# SENSE_AMP_-_4_CH.net
KiCad netlist of a schematic drawn in Altium Designer
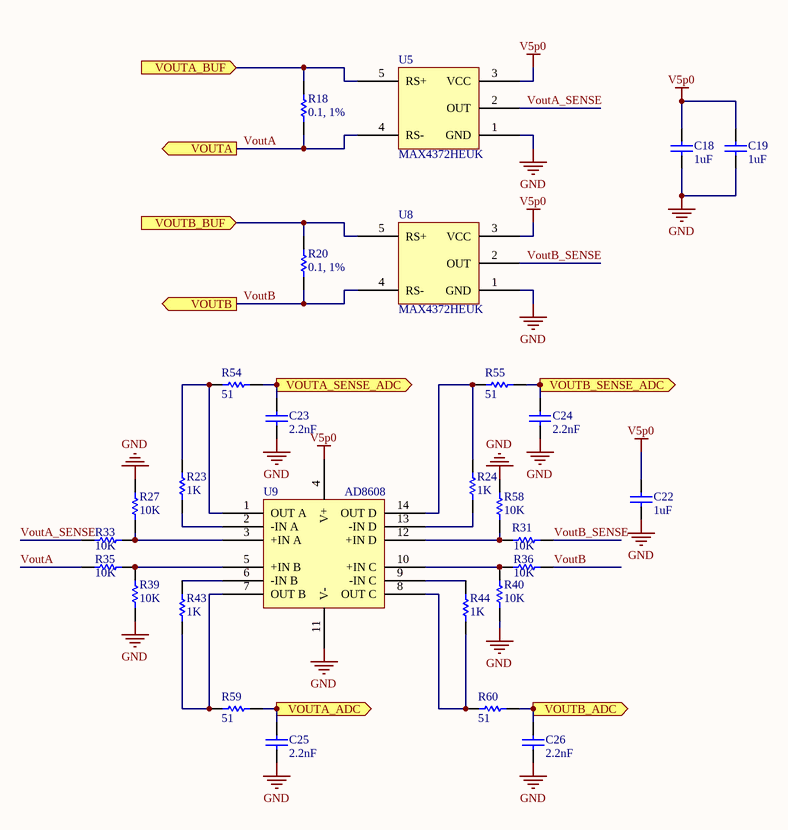
[diagram p0: SENSE AMP - 4 CH.SchDoc]

(export (version "E")
  (design (tool "Eeschema 10.0.6"))
  (components
    (comp (ref "C18")
      (value "1uF")
      (footprint "CAPC01005(0402)22_N")
      (fields (field (name "Comment") "CAP, 0402, 1uF"))
      (libsource (lib "Components") (part "CAP, 0402, 1uF"))
    )
    (comp (ref "C19")
      (value "1uF")
      (footprint "CAPC01005(0402)22_N")
      (fields (field (name "Comment") "CAP, 0402, 1uF"))
      (libsource (lib "Components") (part "CAP, 0402, 1uF"))
    )
    (comp (ref "C22")
      (value "1uF")
      (footprint "CAPC01005(0402)22_N")
      (fields (field (name "Comment") "CAP, 0402, 1uF"))
      (libsource (lib "Components") (part "CAP, 0402, 1uF"))
    )
    (comp (ref "C23")
      (value "2.2nF")
      (footprint "CAPC01005(0402)22_N")
      (fields
        (field (name "TOLERANCE") "±10%")
        (field (name "MANUFACTURER") "Taiyo Yuden")
        (field (name "MANUFACTURER PART NUMBER") "UMK105B7222KV-F")
      )
      (libsource (lib "Components") (part "CAP, 0402, 2.2nF"))
    )
    (comp (ref "C24")
      (value "2.2nF")
      (footprint "CAPC01005(0402)22_N")
      (fields
        (field (name "TOLERANCE") "±10%")
        (field (name "MANUFACTURER") "Taiyo Yuden")
        (field (name "MANUFACTURER PART NUMBER") "UMK105B7222KV-F")
      )
      (libsource (lib "Components") (part "CAP, 0402, 2.2nF"))
    )
    (comp (ref "C25")
      (value "2.2nF")
      (footprint "CAPC01005(0402)22_N")
      (fields
        (field (name "TOLERANCE") "±10%")
        (field (name "MANUFACTURER") "Taiyo Yuden")
        (field (name "MANUFACTURER PART NUMBER") "UMK105B7222KV-F")
      )
      (libsource (lib "Components") (part "CAP, 0402, 2.2nF"))
    )
    (comp (ref "C26")
      (value "2.2nF")
      (footprint "CAPC01005(0402)22_N")
      (fields
        (field (name "TOLERANCE") "±10%")
        (field (name "MANUFACTURER") "Taiyo Yuden")
        (field (name "MANUFACTURER PART NUMBER") "UMK105B7222KV-F")
      )
      (libsource (lib "Components") (part "CAP, 0402, 2.2nF"))
    )
    (comp (ref "R18")
      (value "0.1, 1%")
      (footprint "RES, 0603")
      (fields
        (field (name "TOLERANCE") "±1%")
        (field (name "MANUFACTURER") "Panasonic Electronic Components")
        (field (name "MANUFACTURER PART NUMBER") "ERJ-3RSFR10V")
      )
      (libsource (lib "Components") (part "RES, 0603, 0.1, 1%"))
    )
    (comp (ref "R20")
      (value "0.1, 1%")
      (footprint "RES, 0603")
      (fields
        (field (name "TOLERANCE") "±1%")
        (field (name "MANUFACTURER") "Panasonic Electronic Components")
        (field (name "MANUFACTURER PART NUMBER") "ERJ-3RSFR10V")
      )
      (libsource (lib "Components") (part "RES, 0603, 0.1, 1%"))
    )
    (comp (ref "R23")
      (value "1K")
      (footprint "RES, 0603")
      (description "Resistor, 0603, 1/10W, 1K ohm")
      (fields
        (field (name "MANUFACTURER") "Panasonic Electronic Components")
        (field (name "MANUFACTURER PART NUMBER") "ERJ-3EKF1001V")
      )
      (libsource (lib "Resistors0603") (part "RES_0603_1K"))
    )
    (comp (ref "R24")
      (value "1K")
      (footprint "RES, 0603")
      (description "Resistor, 0603, 1/10W, 1K ohm")
      (fields
        (field (name "MANUFACTURER") "Panasonic Electronic Components")
        (field (name "MANUFACTURER PART NUMBER") "ERJ-3EKF1001V")
      )
      (libsource (lib "Resistors0603") (part "RES_0603_1K"))
    )
    (comp (ref "R27")
      (value "10K")
      (footprint "RES, 0603")
      (description "Resistor, 0603, 1/10W, 10K ohm")
      (fields
        (field (name "MANUFACTURER") "Panasonic Electronic Components")
        (field (name "MANUFACTURER PART NUMBER") "ERJ-3EKF1002V")
      )
      (libsource (lib "Resistors0603") (part "RES_0603_10K"))
    )
    (comp (ref "R31")
      (value "10K")
      (footprint "RES, 0603")
      (description "Resistor, 0603, 1/10W, 10K ohm")
      (fields
        (field (name "MANUFACTURER") "Panasonic Electronic Components")
        (field (name "MANUFACTURER PART NUMBER") "ERJ-3EKF1002V")
      )
      (libsource (lib "Resistors0603") (part "RES_0603_10K"))
    )
    (comp (ref "R33")
      (value "10K")
      (footprint "RES, 0603")
      (description "Resistor, 0603, 1/10W, 10K ohm")
      (fields
        (field (name "MANUFACTURER") "Panasonic Electronic Components")
        (field (name "MANUFACTURER PART NUMBER") "ERJ-3EKF1002V")
      )
      (libsource (lib "Resistors0603") (part "RES_0603_10K"))
    )
    (comp (ref "R35")
      (value "10K")
      (footprint "RES, 0603")
      (description "Resistor, 0603, 1/10W, 10K ohm")
      (fields
        (field (name "MANUFACTURER") "Panasonic Electronic Components")
        (field (name "MANUFACTURER PART NUMBER") "ERJ-3EKF1002V")
      )
      (libsource (lib "Resistors0603") (part "RES_0603_10K"))
    )
    (comp (ref "R36")
      (value "10K")
      (footprint "RES, 0603")
      (description "Resistor, 0603, 1/10W, 10K ohm")
      (fields
        (field (name "MANUFACTURER") "Panasonic Electronic Components")
        (field (name "MANUFACTURER PART NUMBER") "ERJ-3EKF1002V")
      )
      (libsource (lib "Resistors0603") (part "RES_0603_10K"))
    )
    (comp (ref "R39")
      (value "10K")
      (footprint "RES, 0603")
      (description "Resistor, 0603, 1/10W, 10K ohm")
      (fields
        (field (name "MANUFACTURER") "Panasonic Electronic Components")
        (field (name "MANUFACTURER PART NUMBER") "ERJ-3EKF1002V")
      )
      (libsource (lib "Resistors0603") (part "RES_0603_10K"))
    )
    (comp (ref "R40")
      (value "10K")
      (footprint "RES, 0603")
      (description "Resistor, 0603, 1/10W, 10K ohm")
      (fields
        (field (name "MANUFACTURER") "Panasonic Electronic Components")
        (field (name "MANUFACTURER PART NUMBER") "ERJ-3EKF1002V")
      )
      (libsource (lib "Resistors0603") (part "RES_0603_10K"))
    )
    (comp (ref "R43")
      (value "1K")
      (footprint "RES, 0603")
      (description "Resistor, 0603, 1/10W, 1K ohm")
      (fields
        (field (name "MANUFACTURER") "Panasonic Electronic Components")
        (field (name "MANUFACTURER PART NUMBER") "ERJ-3EKF1001V")
      )
      (libsource (lib "Resistors0603") (part "RES_0603_1K"))
    )
    (comp (ref "R44")
      (value "1K")
      (footprint "RES, 0603")
      (description "Resistor, 0603, 1/10W, 1K ohm")
      (fields
        (field (name "MANUFACTURER") "Panasonic Electronic Components")
        (field (name "MANUFACTURER PART NUMBER") "ERJ-3EKF1001V")
      )
      (libsource (lib "Resistors0603") (part "RES_0603_1K"))
    )
    (comp (ref "R54")
      (value "51")
      (footprint "RES, 0603")
      (description "Resistor, 0603, 1/10W, 51 ohm")
      (fields
        (field (name "MANUFACTURER") "Panasonic Electronic Components")
        (field (name "MANUFACTURER PART NUMBER") "ERJ-3EKF51R0V")
      )
      (libsource (lib "Resistors0603") (part "RES_0603_51"))
    )
    (comp (ref "R55")
      (value "51")
      (footprint "RES, 0603")
      (description "Resistor, 0603, 1/10W, 51 ohm")
      (fields
        (field (name "MANUFACTURER") "Panasonic Electronic Components")
        (field (name "MANUFACTURER PART NUMBER") "ERJ-3EKF51R0V")
      )
      (libsource (lib "Resistors0603") (part "RES_0603_51"))
    )
    (comp (ref "R58")
      (value "10K")
      (footprint "RES, 0603")
      (description "Resistor, 0603, 1/10W, 10K ohm")
      (fields
        (field (name "MANUFACTURER") "Panasonic Electronic Components")
        (field (name "MANUFACTURER PART NUMBER") "ERJ-3EKF1002V")
      )
      (libsource (lib "Resistors0603") (part "RES_0603_10K"))
    )
    (comp (ref "R59")
      (value "51")
      (footprint "RES, 0603")
      (description "Resistor, 0603, 1/10W, 51 ohm")
      (fields
        (field (name "MANUFACTURER") "Panasonic Electronic Components")
        (field (name "MANUFACTURER PART NUMBER") "ERJ-3EKF51R0V")
      )
      (libsource (lib "Resistors0603") (part "RES_0603_51"))
    )
    (comp (ref "R60")
      (value "51")
      (footprint "RES, 0603")
      (description "Resistor, 0603, 1/10W, 51 ohm")
      (fields
        (field (name "MANUFACTURER") "Panasonic Electronic Components")
        (field (name "MANUFACTURER PART NUMBER") "ERJ-3EKF51R0V")
      )
      (libsource (lib "Resistors0603") (part "RES_0603_51"))
    )
    (comp (ref "U5")
      (value "MAX4372HEUK")
      (footprint "SOT23-5, MAX4372H")
      (fields (field (name "MANUFACTURER") "Maxim"))
      (libsource (lib "Components") (part "MAX4372H, Current-Sense, SOT23"))
    )
    (comp (ref "U8")
      (value "MAX4372HEUK")
      (footprint "SOT23-5, MAX4372H")
      (fields (field (name "MANUFACTURER") "Maxim"))
      (libsource (lib "Components") (part "MAX4372H, Current-Sense, SOT23"))
    )
    (comp (ref "U9")
      (value "AD8608")
      (footprint "TSOP65P640X120-14N")
      (description "Quad Op-Amp")
      (fields
        (field (name "MANUFACTURER") "Analog Devices Inc")
        (field (name "MANUFACTURER PART NUMBER") "AD8608ARZ-REEL")
      )
      (libsource (lib "Components") (part "AD8608"))
    )
  )
  (nets
    (net (code "1") (name "/VOUTA_ADC") (class "Default")
      (node (ref "C25") (pin "2") (pinfunction "2_2") (pintype "passive"))
      (node (ref "R59") (pin "2") (pinfunction "2_2") (pintype "passive"))
    )
    (net (code "2") (name "/VOUTA_BUF") (class "Default")
      (node (ref "R18") (pin "2") (pinfunction "2_2") (pintype "passive"))
      (node (ref "U5") (pin "5") (pinfunction "RS+_5") (pintype "passive"))
    )
    (net (code "3") (name "/VOUTA_SENSE_ADC") (class "Default")
      (node (ref "C23") (pin "2") (pinfunction "2_2") (pintype "passive"))
      (node (ref "R54") (pin "2") (pinfunction "2_2") (pintype "passive"))
    )
    (net (code "4") (name "/VOUTB_ADC") (class "Default")
      (node (ref "C26") (pin "2") (pinfunction "2_2") (pintype "passive"))
      (node (ref "R60") (pin "2") (pinfunction "2_2") (pintype "passive"))
    )
    (net (code "5") (name "/VOUTB_BUF") (class "Default")
      (node (ref "R20") (pin "2") (pinfunction "2_2") (pintype "passive"))
      (node (ref "U8") (pin "5") (pinfunction "RS+_5") (pintype "passive"))
    )
    (net (code "6") (name "/VOUTB_SENSE_ADC") (class "Default")
      (node (ref "C24") (pin "2") (pinfunction "2_2") (pintype "passive"))
      (node (ref "R55") (pin "2") (pinfunction "2_2") (pintype "passive"))
    )
    (net (code "7") (name "/VoutA") (class "Default")
      (node (ref "R18") (pin "1") (pinfunction "1_1") (pintype "passive"))
      (node (ref "R35") (pin "1") (pinfunction "1_1") (pintype "passive"))
      (node (ref "U5") (pin "4") (pinfunction "RS-_4") (pintype "passive"))
    )
    (net (code "8") (name "/VoutA_SENSE") (class "Default")
      (node (ref "R33") (pin "1") (pinfunction "1_1") (pintype "passive"))
      (node (ref "U5") (pin "2") (pinfunction "OUT_2") (pintype "passive"))
    )
    (net (code "9") (name "/VoutB") (class "Default")
      (node (ref "R20") (pin "1") (pinfunction "1_1") (pintype "passive"))
      (node (ref "R36") (pin "1") (pinfunction "1_1") (pintype "passive"))
      (node (ref "U8") (pin "4") (pinfunction "RS-_4") (pintype "passive"))
    )
    (net (code "10") (name "/VoutB_SENSE") (class "Default")
      (node (ref "R31") (pin "1") (pinfunction "1_1") (pintype "passive"))
      (node (ref "U8") (pin "2") (pinfunction "OUT_2") (pintype "passive"))
    )
    (net (code "11") (name "GND") (class "Default")
      (node (ref "C18") (pin "1") (pinfunction "1_1") (pintype "passive"))
      (node (ref "C19") (pin "1") (pinfunction "1_1") (pintype "passive"))
      (node (ref "C22") (pin "1") (pinfunction "1_1") (pintype "passive"))
      (node (ref "C23") (pin "1") (pinfunction "1_1") (pintype "passive"))
      (node (ref "C24") (pin "1") (pinfunction "1_1") (pintype "passive"))
      (node (ref "C25") (pin "1") (pinfunction "1_1") (pintype "passive"))
      (node (ref "C26") (pin "1") (pinfunction "1_1") (pintype "passive"))
      (node (ref "R27") (pin "2") (pinfunction "2_2") (pintype "passive"))
      (node (ref "R39") (pin "1") (pinfunction "1_1") (pintype "passive"))
      (node (ref "R40") (pin "2") (pinfunction "2_2") (pintype "passive"))
      (node (ref "R58") (pin "1") (pinfunction "1_1") (pintype "passive"))
      (node (ref "U5") (pin "1") (pinfunction "GND_1") (pintype "passive"))
      (node (ref "U8") (pin "1") (pinfunction "GND_1") (pintype "passive"))
      (node (ref "U9") (pin "11") (pinfunction "V-_11") (pintype "passive"))
    )
    (net (code "12") (name "Net-(U9-+IN_A)") (class "Default")
      (node (ref "R27") (pin "1") (pinfunction "1_1") (pintype "passive"))
      (node (ref "R33") (pin "2") (pinfunction "2_2") (pintype "passive"))
      (node (ref "U9") (pin "3") (pinfunction "+IN_A_3") (pintype "passive"))
    )
    (net (code "13") (name "Net-(U9-+IN_B)") (class "Default")
      (node (ref "R35") (pin "2") (pinfunction "2_2") (pintype "passive"))
      (node (ref "R39") (pin "2") (pinfunction "2_2") (pintype "passive"))
      (node (ref "U9") (pin "5") (pinfunction "+IN_B_5") (pintype "passive"))
    )
    (net (code "14") (name "Net-(U9-+IN_C)") (class "Default")
      (node (ref "R36") (pin "2") (pinfunction "2_2") (pintype "passive"))
      (node (ref "R40") (pin "1") (pinfunction "1_1") (pintype "passive"))
      (node (ref "U9") (pin "10") (pinfunction "+IN_C_10") (pintype "passive"))
    )
    (net (code "15") (name "Net-(U9-+IN_D)") (class "Default")
      (node (ref "R31") (pin "2") (pinfunction "2_2") (pintype "passive"))
      (node (ref "R58") (pin "2") (pinfunction "2_2") (pintype "passive"))
      (node (ref "U9") (pin "12") (pinfunction "+IN_D_12") (pintype "passive"))
    )
    (net (code "16") (name "Net-(U9--IN_A)") (class "Default")
      (node (ref "R23") (pin "1") (pinfunction "1_1") (pintype "passive"))
      (node (ref "U9") (pin "2") (pinfunction "-IN_A_2") (pintype "passive"))
    )
    (net (code "17") (name "Net-(U9--IN_B)") (class "Default")
      (node (ref "R43") (pin "2") (pinfunction "2_2") (pintype "passive"))
      (node (ref "U9") (pin "6") (pinfunction "-IN_B_6") (pintype "passive"))
    )
    (net (code "18") (name "Net-(U9--IN_C)") (class "Default")
      (node (ref "R44") (pin "2") (pinfunction "2_2") (pintype "passive"))
      (node (ref "U9") (pin "9") (pinfunction "-IN_C_9") (pintype "passive"))
    )
    (net (code "19") (name "Net-(U9--IN_D)") (class "Default")
      (node (ref "R24") (pin "1") (pinfunction "1_1") (pintype "passive"))
      (node (ref "U9") (pin "13") (pinfunction "-IN_D_13") (pintype "passive"))
    )
    (net (code "20") (name "Net-(U9-OUT_A)") (class "Default")
      (node (ref "R23") (pin "2") (pinfunction "2_2") (pintype "passive"))
      (node (ref "R54") (pin "1") (pinfunction "1_1") (pintype "passive"))
      (node (ref "U9") (pin "1") (pinfunction "OUT_A_1") (pintype "passive"))
    )
    (net (code "21") (name "Net-(U9-OUT_B)") (class "Default")
      (node (ref "R43") (pin "1") (pinfunction "1_1") (pintype "passive"))
      (node (ref "R59") (pin "1") (pinfunction "1_1") (pintype "passive"))
      (node (ref "U9") (pin "7") (pinfunction "OUT_B_7") (pintype "passive"))
    )
    (net (code "22") (name "Net-(U9-OUT_C)") (class "Default")
      (node (ref "R44") (pin "1") (pinfunction "1_1") (pintype "passive"))
      (node (ref "R60") (pin "1") (pinfunction "1_1") (pintype "passive"))
      (node (ref "U9") (pin "8") (pinfunction "OUT_C_8") (pintype "passive"))
    )
    (net (code "23") (name "Net-(U9-OUT_D)") (class "Default")
      (node (ref "R24") (pin "2") (pinfunction "2_2") (pintype "passive"))
      (node (ref "R55") (pin "1") (pinfunction "1_1") (pintype "passive"))
      (node (ref "U9") (pin "14") (pinfunction "OUT_D_14") (pintype "passive"))
    )
    (net (code "24") (name "V5p0") (class "Default")
      (node (ref "C18") (pin "2") (pinfunction "2_2") (pintype "passive"))
      (node (ref "C19") (pin "2") (pinfunction "2_2") (pintype "passive"))
      (node (ref "C22") (pin "2") (pinfunction "2_2") (pintype "passive"))
      (node (ref "U5") (pin "3") (pinfunction "VCC_3") (pintype "passive"))
      (node (ref "U8") (pin "3") (pinfunction "VCC_3") (pintype "passive"))
      (node (ref "U9") (pin "4") (pinfunction "V+_4") (pintype "passive"))
    )
  )
)
